# 04B-355.net
KiCad netlist of a schematic drawn in EAGLE
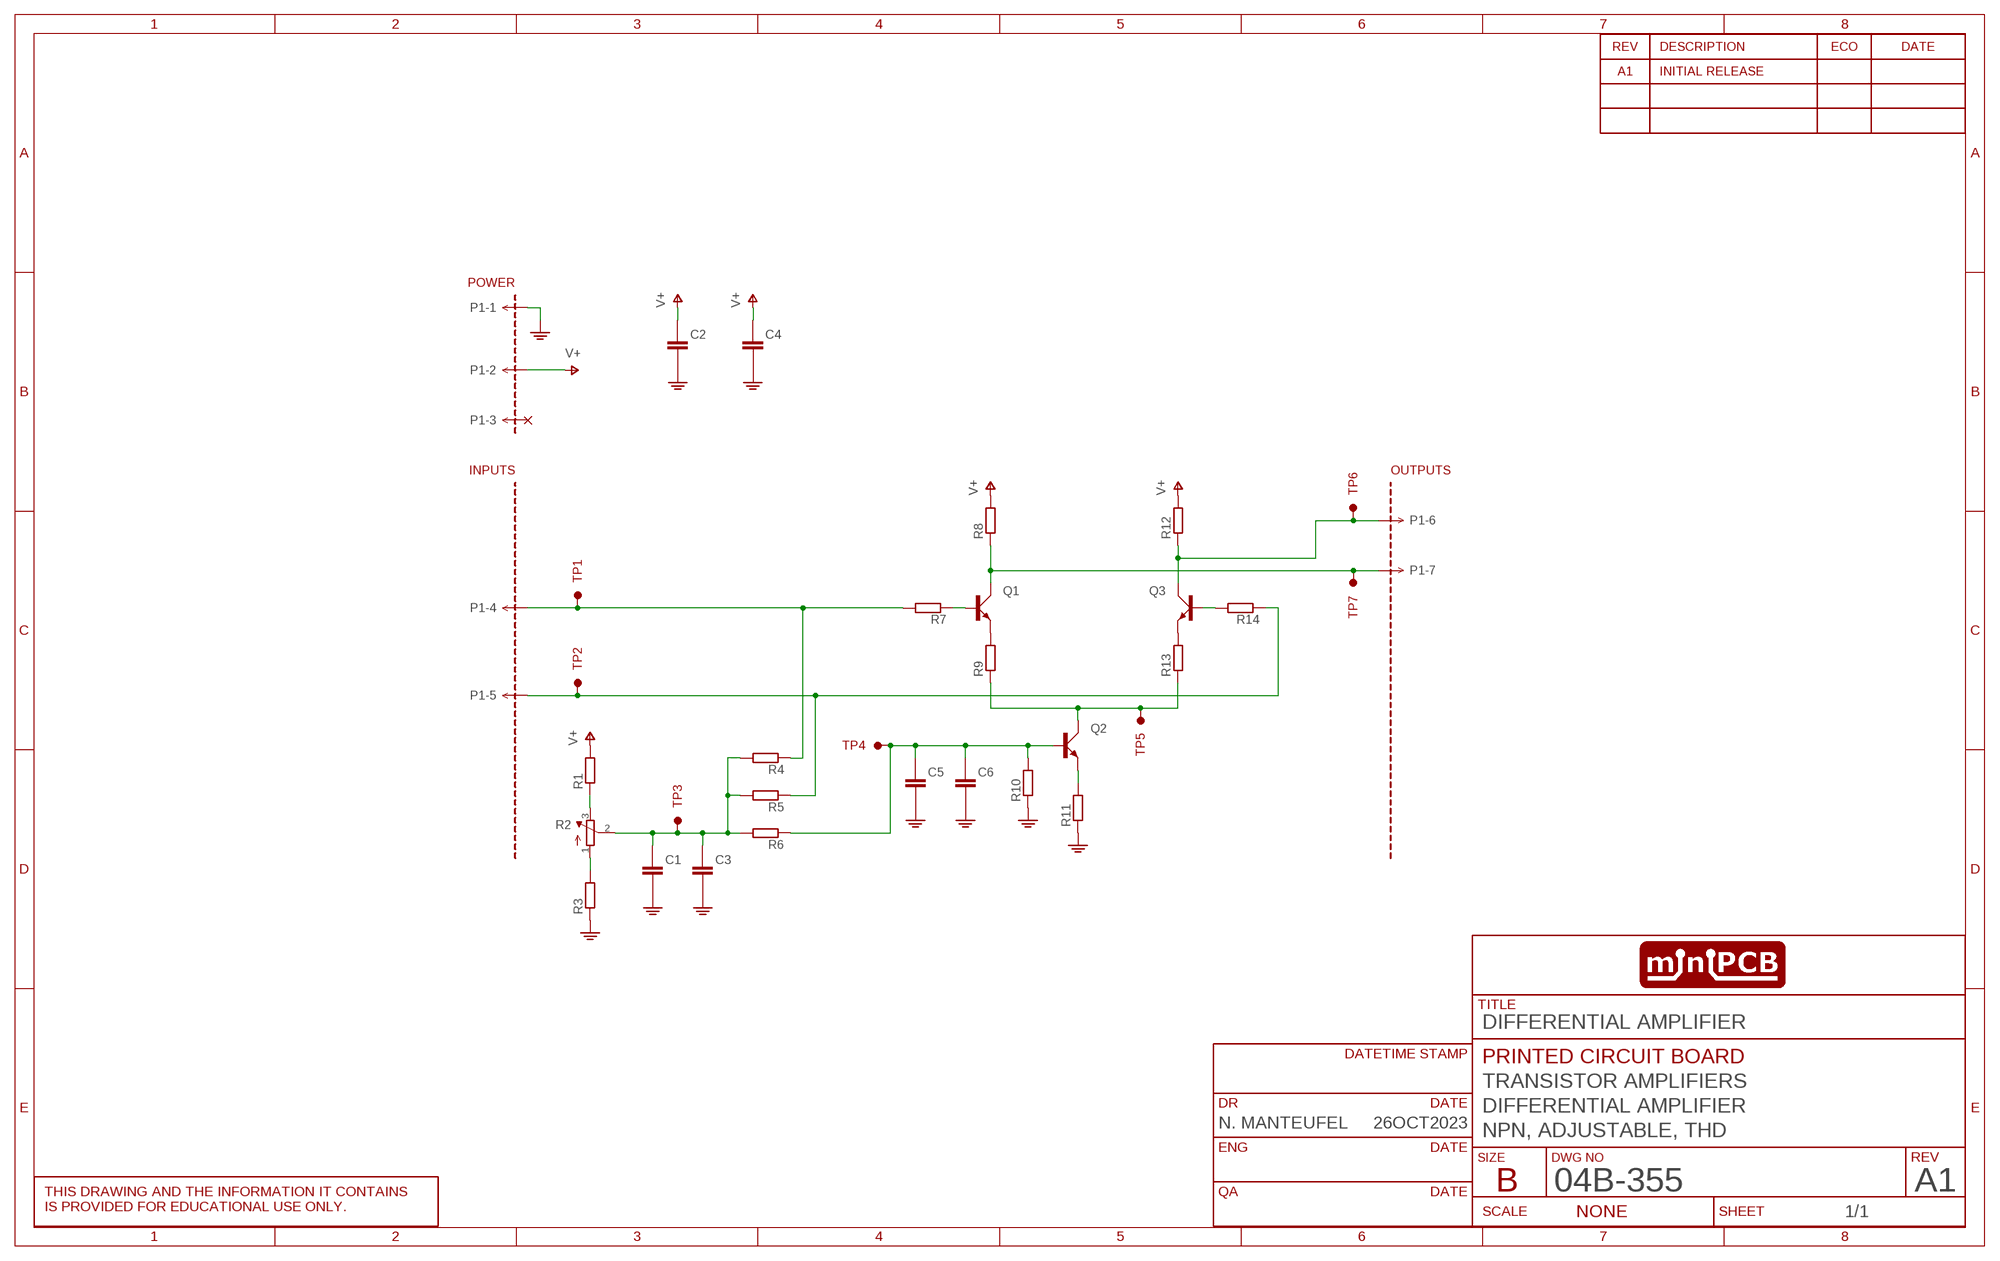
[diagram p0: schematic, sheet 1]

(export (version "E")
  (design (tool "Eeschema 10.0.6"))
  (components
    (comp (ref "C1")
      (value "CAPACITORTHD")
      (footprint "eagle-import:C050-024X044")
      (libsource (lib "eagle-import") (part "CAPACITORTHD"))
    )
    (comp (ref "C2")
      (value "CAPACITORTHD")
      (footprint "eagle-import:C050-024X044")
      (libsource (lib "eagle-import") (part "CAPACITORTHD"))
    )
    (comp (ref "C3")
      (value "CAPACITOR_10")
      (footprint "eagle-import:C5MM")
      (libsource (lib "eagle-import") (part "CAPACITOR_10"))
    )
    (comp (ref "C4")
      (value "CAPACITOR_10")
      (footprint "eagle-import:C5MM")
      (libsource (lib "eagle-import") (part "CAPACITOR_10"))
    )
    (comp (ref "C5")
      (value "CAPACITORTHD")
      (footprint "eagle-import:C050-024X044")
      (libsource (lib "eagle-import") (part "CAPACITORTHD"))
    )
    (comp (ref "C6")
      (value "CAPACITOR_10")
      (footprint "eagle-import:C5MM")
      (libsource (lib "eagle-import") (part "CAPACITOR_10"))
    )
    (comp (ref "P1")
      (value "MINIPCB_7P")
      (footprint "eagle-import:PINS_1X7")
      (libsource (lib "eagle-import") (part "MINIPCB_7P"))
    )
    (comp (ref "PCB1")
      (value "MINIPCB_0P50X75")
      (footprint "eagle-import:MINIPCB_0P_50X75")
      (libsource (lib "eagle-import") (part "MINIPCB_0P50X75"))
    )
    (comp (ref "Q1")
      (value "BJT_NPNEBC")
      (footprint "eagle-import:TO92-EBC-OVAL")
      (libsource (lib "eagle-import") (part "BJT_NPNEBC"))
    )
    (comp (ref "Q2")
      (value "BJT_NPNEBC")
      (footprint "eagle-import:TO92-EBC-OVAL")
      (libsource (lib "eagle-import") (part "BJT_NPNEBC"))
    )
    (comp (ref "Q3")
      (value "BJT_NPNEBC")
      (footprint "eagle-import:TO92-EBC-OVAL")
      (libsource (lib "eagle-import") (part "BJT_NPNEBC"))
    )
    (comp (ref "R1")
      (value "RESISTORTHD")
      (footprint "eagle-import:0204_10")
      (libsource (lib "eagle-import") (part "RESISTORTHD"))
    )
    (comp (ref "R2")
      (value "TRIMPOT0.100THD")
      (footprint "eagle-import:TRIM_0100")
      (libsource (lib "eagle-import") (part "TRIMPOT0.100THD"))
    )
    (comp (ref "R3")
      (value "RESISTORTHD")
      (footprint "eagle-import:0204_10")
      (libsource (lib "eagle-import") (part "RESISTORTHD"))
    )
    (comp (ref "R4")
      (value "RESISTORTHD")
      (footprint "eagle-import:0204_10")
      (libsource (lib "eagle-import") (part "RESISTORTHD"))
    )
    (comp (ref "R5")
      (value "RESISTORTHD")
      (footprint "eagle-import:0204_10")
      (libsource (lib "eagle-import") (part "RESISTORTHD"))
    )
    (comp (ref "R6")
      (value "RESISTORTHD")
      (footprint "eagle-import:0204_10")
      (libsource (lib "eagle-import") (part "RESISTORTHD"))
    )
    (comp (ref "R7")
      (value "RESISTORTHD")
      (footprint "eagle-import:0204_10")
      (libsource (lib "eagle-import") (part "RESISTORTHD"))
    )
    (comp (ref "R8")
      (value "RESISTORTHD")
      (footprint "eagle-import:0204_10")
      (libsource (lib "eagle-import") (part "RESISTORTHD"))
    )
    (comp (ref "R9")
      (value "RESISTORTHD")
      (footprint "eagle-import:0204_10")
      (libsource (lib "eagle-import") (part "RESISTORTHD"))
    )
    (comp (ref "R10")
      (value "RESISTORTHD")
      (footprint "eagle-import:0204_10")
      (libsource (lib "eagle-import") (part "RESISTORTHD"))
    )
    (comp (ref "R11")
      (value "RESISTORTHD")
      (footprint "eagle-import:0204_10")
      (libsource (lib "eagle-import") (part "RESISTORTHD"))
    )
    (comp (ref "R12")
      (value "RESISTORTHD")
      (footprint "eagle-import:0204_10")
      (libsource (lib "eagle-import") (part "RESISTORTHD"))
    )
    (comp (ref "R13")
      (value "RESISTORTHD")
      (footprint "eagle-import:0204_10")
      (libsource (lib "eagle-import") (part "RESISTORTHD"))
    )
    (comp (ref "R14")
      (value "RESISTORTHD")
      (footprint "eagle-import:0204_10")
      (libsource (lib "eagle-import") (part "RESISTORTHD"))
    )
    (comp (ref "TP1")
      (value "TESTPOINTKE5000-SMTEXT")
      (footprint "eagle-import:PINS_1_TESTPOINT_KE5000_NOTEXT")
      (libsource (lib "eagle-import") (part "TESTPOINTKE5000-SMTEXT"))
    )
    (comp (ref "TP2")
      (value "TESTPOINTKE5000-SMTEXT")
      (footprint "eagle-import:PINS_1_TESTPOINT_KE5000_NOTEXT")
      (libsource (lib "eagle-import") (part "TESTPOINTKE5000-SMTEXT"))
    )
    (comp (ref "TP3")
      (value "TESTPOINTKE5000-SMTEXT")
      (footprint "eagle-import:PINS_1_TESTPOINT_KE5000_NOTEXT")
      (libsource (lib "eagle-import") (part "TESTPOINTKE5000-SMTEXT"))
    )
    (comp (ref "TP4")
      (value "TESTPOINTKE5000-SMTEXT")
      (footprint "eagle-import:PINS_1_TESTPOINT_KE5000_NOTEXT")
      (libsource (lib "eagle-import") (part "TESTPOINTKE5000-SMTEXT"))
    )
    (comp (ref "TP5")
      (value "TESTPOINTKE5000-SMTEXT")
      (footprint "eagle-import:PINS_1_TESTPOINT_KE5000_NOTEXT")
      (libsource (lib "eagle-import") (part "TESTPOINTKE5000-SMTEXT"))
    )
    (comp (ref "TP6")
      (value "TESTPOINTKE5000-SMTEXT")
      (footprint "eagle-import:PINS_1_TESTPOINT_KE5000_NOTEXT")
      (libsource (lib "eagle-import") (part "TESTPOINTKE5000-SMTEXT"))
    )
    (comp (ref "TP7")
      (value "TESTPOINTKE5000-SMTEXT")
      (footprint "eagle-import:PINS_1_TESTPOINT_KE5000_NOTEXT")
      (libsource (lib "eagle-import") (part "TESTPOINTKE5000-SMTEXT"))
    )
  )
  (nets
    (net (code "1") (name "GND") (class "Default")
      (node (ref "C1") (pin "2") (pinfunction "-_2") (pintype "passive"))
      (node (ref "C2") (pin "2") (pinfunction "-_2") (pintype "passive"))
      (node (ref "C3") (pin "-") (pinfunction "-_-") (pintype "passive"))
      (node (ref "C4") (pin "-") (pinfunction "-_-") (pintype "passive"))
      (node (ref "C5") (pin "2") (pinfunction "-_2") (pintype "passive"))
      (node (ref "C6") (pin "-") (pinfunction "-_-") (pintype "passive"))
      (node (ref "P1") (pin "1") (pinfunction "1_1") (pintype "bidirectional"))
      (node (ref "R10") (pin "1") (pinfunction "1_1") (pintype "passive"))
      (node (ref "R11") (pin "1") (pinfunction "1_1") (pintype "passive"))
      (node (ref "R3") (pin "1") (pinfunction "1_1") (pintype "passive"))
    )
    (net (code "2") (name "Net-(C1-+)") (class "Default")
      (node (ref "C1") (pin "1") (pinfunction "+_1") (pintype "passive"))
      (node (ref "C3") (pin "+") (pinfunction "+_+") (pintype "passive"))
      (node (ref "R2") (pin "2") (pinfunction "S_2") (pintype "passive"))
      (node (ref "R4") (pin "2") (pinfunction "2_2") (pintype "passive"))
      (node (ref "R5") (pin "2") (pinfunction "2_2") (pintype "passive"))
      (node (ref "R6") (pin "2") (pinfunction "2_2") (pintype "passive"))
      (node (ref "TP3") (pin "1") (pinfunction "1_1") (pintype "bidirectional"))
    )
    (net (code "3") (name "Net-(C5-+)") (class "Default")
      (node (ref "C5") (pin "1") (pinfunction "+_1") (pintype "passive"))
      (node (ref "C6") (pin "+") (pinfunction "+_+") (pintype "passive"))
      (node (ref "Q2") (pin "B") (pinfunction "B_B") (pintype "passive"))
      (node (ref "R10") (pin "2") (pinfunction "2_2") (pintype "passive"))
      (node (ref "R6") (pin "1") (pinfunction "1_1") (pintype "passive"))
      (node (ref "TP4") (pin "1") (pinfunction "1_1") (pintype "bidirectional"))
    )
    (net (code "4") (name "Net-(P1D-1)") (class "Default")
      (node (ref "P1") (pin "4") (pinfunction "1_4") (pintype "bidirectional"))
      (node (ref "R4") (pin "1") (pinfunction "1_1") (pintype "passive"))
      (node (ref "R7") (pin "2") (pinfunction "2_2") (pintype "passive"))
      (node (ref "TP1") (pin "1") (pinfunction "1_1") (pintype "bidirectional"))
    )
    (net (code "5") (name "Net-(P1E-1)") (class "Default")
      (node (ref "P1") (pin "5") (pinfunction "1_5") (pintype "bidirectional"))
      (node (ref "R14") (pin "1") (pinfunction "1_1") (pintype "passive"))
      (node (ref "R5") (pin "1") (pinfunction "1_1") (pintype "passive"))
      (node (ref "TP2") (pin "1") (pinfunction "1_1") (pintype "bidirectional"))
    )
    (net (code "6") (name "Net-(P1F-1)") (class "Default")
      (node (ref "P1") (pin "6") (pinfunction "1_6") (pintype "bidirectional"))
      (node (ref "Q3") (pin "C") (pinfunction "C_C") (pintype "passive"))
      (node (ref "R12") (pin "1") (pinfunction "1_1") (pintype "passive"))
      (node (ref "TP6") (pin "1") (pinfunction "1_1") (pintype "bidirectional"))
    )
    (net (code "7") (name "Net-(P1G-1)") (class "Default")
      (node (ref "P1") (pin "7") (pinfunction "1_7") (pintype "bidirectional"))
      (node (ref "Q1") (pin "C") (pinfunction "C_C") (pintype "passive"))
      (node (ref "R8") (pin "1") (pinfunction "1_1") (pintype "passive"))
      (node (ref "TP7") (pin "1") (pinfunction "1_1") (pintype "bidirectional"))
    )
    (net (code "8") (name "Net-(Q1-PadB)") (class "Default")
      (node (ref "Q1") (pin "B") (pinfunction "B_B") (pintype "passive"))
      (node (ref "R7") (pin "1") (pinfunction "1_1") (pintype "passive"))
    )
    (net (code "9") (name "Net-(Q1-PadE)") (class "Default")
      (node (ref "Q1") (pin "E") (pinfunction "E_E") (pintype "passive"))
      (node (ref "R9") (pin "2") (pinfunction "2_2") (pintype "passive"))
    )
    (net (code "10") (name "Net-(Q2-PadC)") (class "Default")
      (node (ref "Q2") (pin "C") (pinfunction "C_C") (pintype "passive"))
      (node (ref "R13") (pin "1") (pinfunction "1_1") (pintype "passive"))
      (node (ref "R9") (pin "1") (pinfunction "1_1") (pintype "passive"))
      (node (ref "TP5") (pin "1") (pinfunction "1_1") (pintype "bidirectional"))
    )
    (net (code "11") (name "Net-(Q2-PadE)") (class "Default")
      (node (ref "Q2") (pin "E") (pinfunction "E_E") (pintype "passive"))
      (node (ref "R11") (pin "2") (pinfunction "2_2") (pintype "passive"))
    )
    (net (code "12") (name "Net-(Q3-PadB)") (class "Default")
      (node (ref "Q3") (pin "B") (pinfunction "B_B") (pintype "passive"))
      (node (ref "R14") (pin "2") (pinfunction "2_2") (pintype "passive"))
    )
    (net (code "13") (name "Net-(Q3-PadE)") (class "Default")
      (node (ref "Q3") (pin "E") (pinfunction "E_E") (pintype "passive"))
      (node (ref "R13") (pin "2") (pinfunction "2_2") (pintype "passive"))
    )
    (net (code "14") (name "Net-(R2-A)") (class "Default")
      (node (ref "R2") (pin "1") (pinfunction "A_1") (pintype "passive"))
      (node (ref "R3") (pin "2") (pinfunction "2_2") (pintype "passive"))
    )
    (net (code "15") (name "Net-(R2-E)") (class "Default")
      (node (ref "R1") (pin "1") (pinfunction "1_1") (pintype "passive"))
      (node (ref "R2") (pin "3") (pinfunction "E_3") (pintype "passive"))
    )
    (net (code "16") (name "V+") (class "Default")
      (node (ref "C2") (pin "1") (pinfunction "+_1") (pintype "passive"))
      (node (ref "C4") (pin "+") (pinfunction "+_+") (pintype "passive"))
      (node (ref "P1") (pin "2") (pinfunction "1_2") (pintype "bidirectional"))
      (node (ref "R1") (pin "2") (pinfunction "2_2") (pintype "passive"))
      (node (ref "R12") (pin "2") (pinfunction "2_2") (pintype "passive"))
      (node (ref "R8") (pin "2") (pinfunction "2_2") (pintype "passive"))
    )
    (net (code "17") (name "unconnected-(P1C-1-Pad3)") (class "Default")
      (node (ref "P1") (pin "3") (pinfunction "1_3") (pintype "bidirectional"))
    )
  )
)
